# untitled.net
KiCad netlist of a schematic drawn in EAGLE
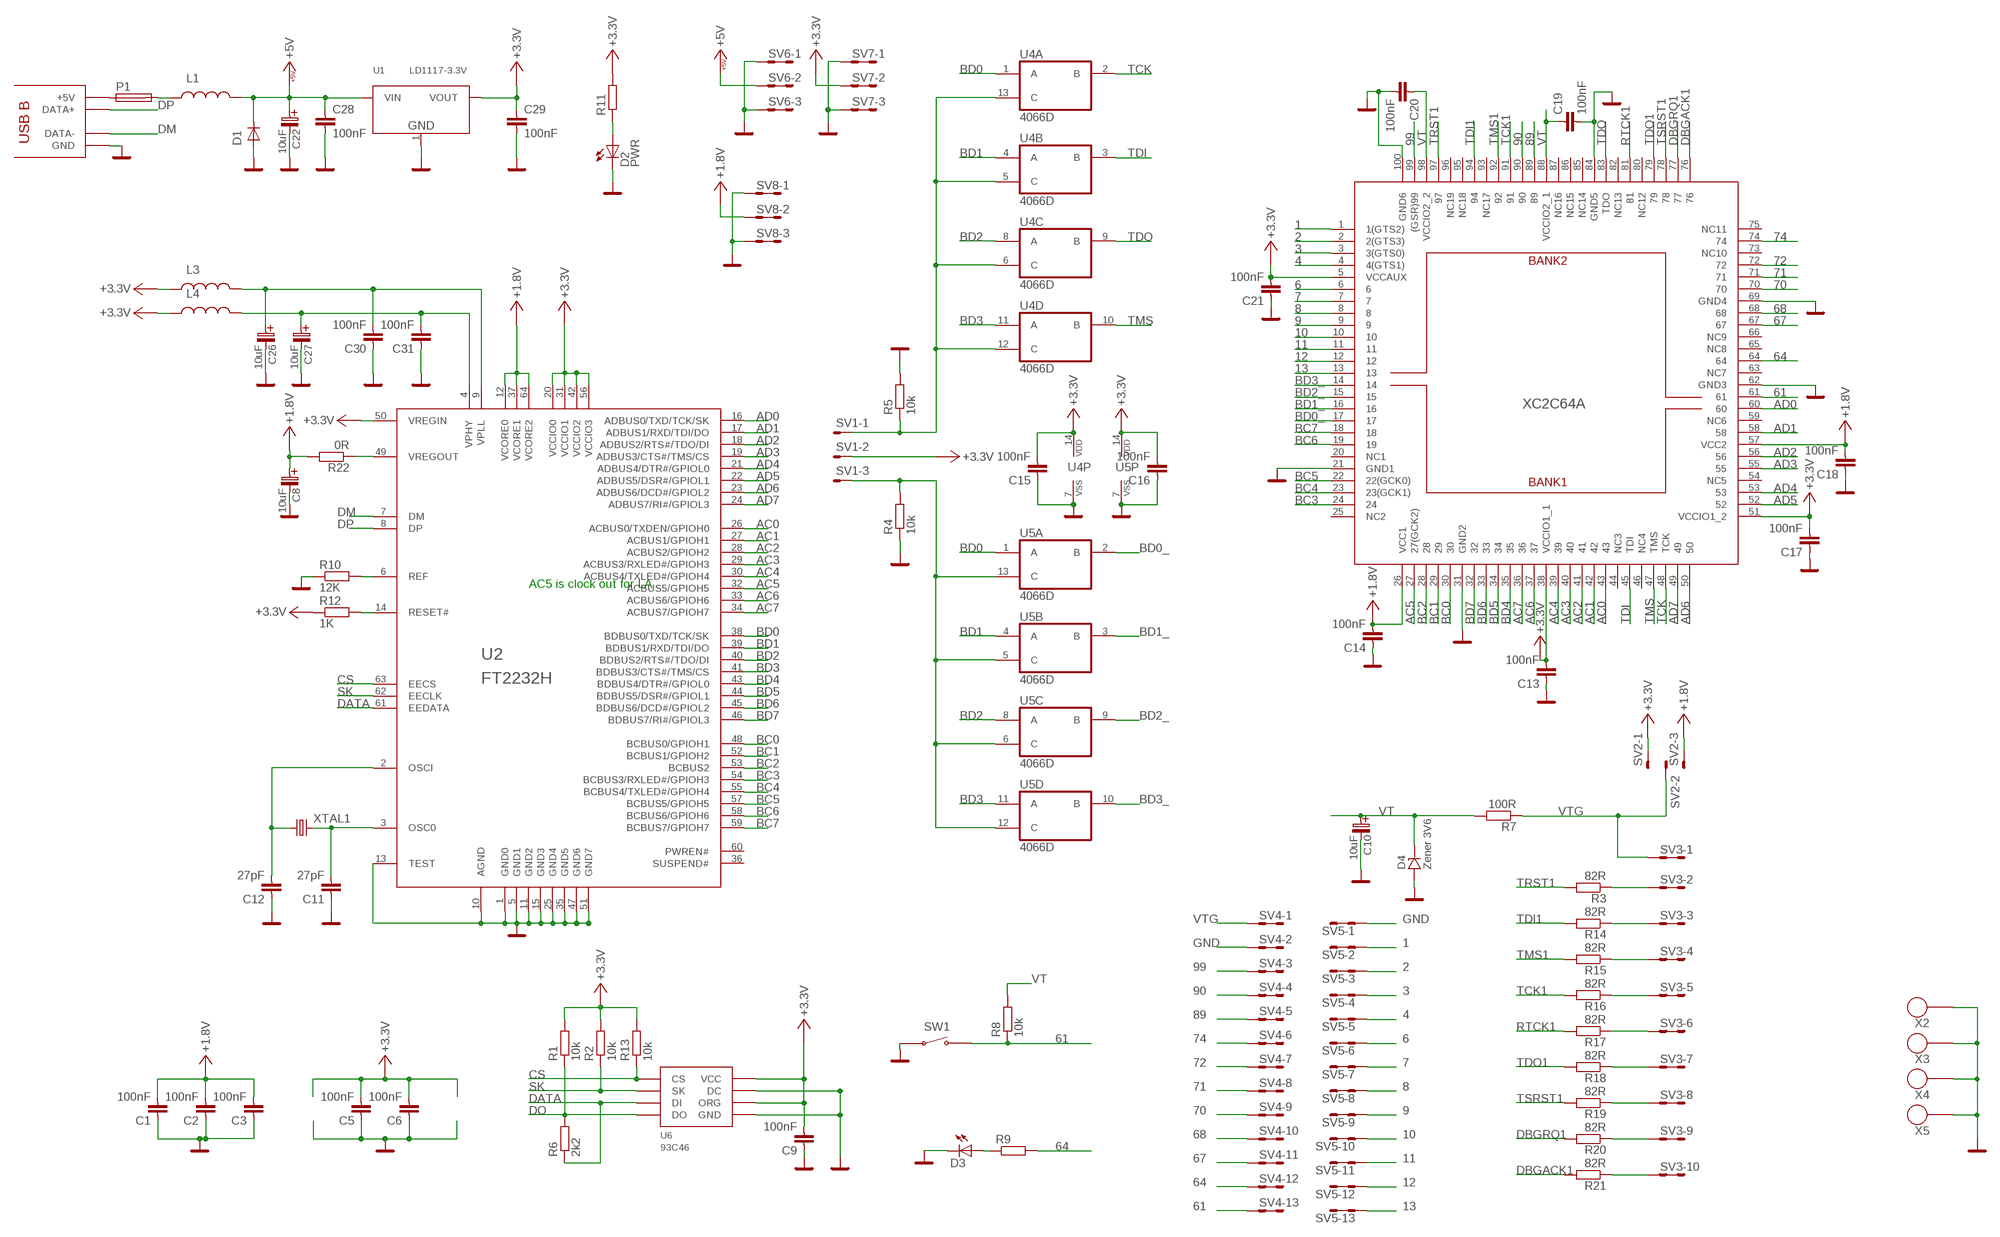
[diagram p0: schematic, sheet 1]

(export (version "E")
  (design (tool "Eeschema 10.0.6"))
  (components
    (comp (ref "C1")
      (value "100nF")
      (footprint "eagle-import:C0805")
      (libsource (lib "eagle-import") (part "C0805"))
    )
    (comp (ref "C2")
      (value "100nF")
      (footprint "eagle-import:C0805")
      (libsource (lib "eagle-import") (part "C0805"))
    )
    (comp (ref "C3")
      (value "100nF")
      (footprint "eagle-import:C0805")
      (libsource (lib "eagle-import") (part "C0805"))
    )
    (comp (ref "C5")
      (value "100nF")
      (footprint "eagle-import:C0805")
      (libsource (lib "eagle-import") (part "C0805"))
    )
    (comp (ref "C6")
      (value "100nF")
      (footprint "eagle-import:C0805")
      (libsource (lib "eagle-import") (part "C0805"))
    )
    (comp (ref "C8") (value "10uF") (footprint "eagle-import:B") (libsource (lib "eagle-import") (part "B")))
    (comp (ref "C9")
      (value "100nF")
      (footprint "eagle-import:C0805")
      (libsource (lib "eagle-import") (part "C0805"))
    )
    (comp (ref "C10") (value "10uF") (footprint "eagle-import:B") (libsource (lib "eagle-import") (part "B")))
    (comp (ref "C11")
      (value "27pF")
      (footprint "eagle-import:C0805")
      (libsource (lib "eagle-import") (part "C0805"))
    )
    (comp (ref "C12")
      (value "27pF")
      (footprint "eagle-import:C0805")
      (libsource (lib "eagle-import") (part "C0805"))
    )
    (comp (ref "C13")
      (value "100nF")
      (footprint "eagle-import:C0805")
      (libsource (lib "eagle-import") (part "C0805"))
    )
    (comp (ref "C14")
      (value "100nF")
      (footprint "eagle-import:C0805")
      (libsource (lib "eagle-import") (part "C0805"))
    )
    (comp (ref "C15")
      (value "100nF")
      (footprint "eagle-import:C0805")
      (libsource (lib "eagle-import") (part "C0805"))
    )
    (comp (ref "C16")
      (value "100nF")
      (footprint "eagle-import:C0805")
      (libsource (lib "eagle-import") (part "C0805"))
    )
    (comp (ref "C17")
      (value "100nF")
      (footprint "eagle-import:C0805")
      (libsource (lib "eagle-import") (part "C0805"))
    )
    (comp (ref "C18")
      (value "100nF")
      (footprint "eagle-import:C0805")
      (libsource (lib "eagle-import") (part "C0805"))
    )
    (comp (ref "C19")
      (value "100nF")
      (footprint "eagle-import:C0805")
      (libsource (lib "eagle-import") (part "C0805"))
    )
    (comp (ref "C20")
      (value "100nF")
      (footprint "eagle-import:C0805")
      (libsource (lib "eagle-import") (part "C0805"))
    )
    (comp (ref "C21")
      (value "100nF")
      (footprint "eagle-import:C0805")
      (libsource (lib "eagle-import") (part "C0805"))
    )
    (comp (ref "C22") (value "10uF") (footprint "eagle-import:B") (libsource (lib "eagle-import") (part "B")))
    (comp (ref "C26") (value "10uF") (footprint "eagle-import:B") (libsource (lib "eagle-import") (part "B")))
    (comp (ref "C27") (value "10uF") (footprint "eagle-import:B") (libsource (lib "eagle-import") (part "B")))
    (comp (ref "C28")
      (value "100nF")
      (footprint "eagle-import:C0805")
      (libsource (lib "eagle-import") (part "C0805"))
    )
    (comp (ref "C29")
      (value "100nF")
      (footprint "eagle-import:C0805")
      (libsource (lib "eagle-import") (part "C0805"))
    )
    (comp (ref "C30")
      (value "100nF")
      (footprint "eagle-import:C0805")
      (libsource (lib "eagle-import") (part "C0805"))
    )
    (comp (ref "C31")
      (value "100nF")
      (footprint "eagle-import:C0805")
      (libsource (lib "eagle-import") (part "C0805"))
    )
    (comp (ref "D1")
      (value "D-OB.SMA")
      (footprint "eagle-import:SMA")
      (libsource (lib "eagle-import") (part "D-OB.SMA"))
    )
    (comp (ref "D2")
      (value "PWR")
      (footprint "eagle-import:1206")
      (libsource (lib "eagle-import") (part "LED1206"))
    )
    (comp (ref "D3")
      (value "LED1206")
      (footprint "eagle-import:1206")
      (libsource (lib "eagle-import") (part "LED1206"))
    )
    (comp (ref "D4")
      (value "Zener 3V6")
      (footprint "eagle-import:MINIMELF")
      (libsource (lib "eagle-import") (part "D-ZENEROVA"))
    )
    (comp (ref "L1")
      (value "L0805")
      (footprint "eagle-import:L0805")
      (libsource (lib "eagle-import") (part "L0805"))
    )
    (comp (ref "L3")
      (value "L1210")
      (footprint "eagle-import:1210")
      (libsource (lib "eagle-import") (part "L1210"))
    )
    (comp (ref "L4")
      (value "L1210")
      (footprint "eagle-import:1210")
      (libsource (lib "eagle-import") (part "L1210"))
    )
    (comp (ref "P1")
      (value "POJISTKA_1812")
      (footprint "eagle-import:1812")
      (libsource (lib "eagle-import") (part "POJISTKA_1812"))
    )
    (comp (ref "R1")
      (value "10k")
      (footprint "eagle-import:0805")
      (libsource (lib "eagle-import") (part "R0805"))
    )
    (comp (ref "R2")
      (value "10k")
      (footprint "eagle-import:0805")
      (libsource (lib "eagle-import") (part "R0805"))
    )
    (comp (ref "R3")
      (value "82R")
      (footprint "eagle-import:0805")
      (libsource (lib "eagle-import") (part "R0805"))
    )
    (comp (ref "R4")
      (value "10k")
      (footprint "eagle-import:0805")
      (libsource (lib "eagle-import") (part "R0805"))
    )
    (comp (ref "R5")
      (value "10k")
      (footprint "eagle-import:0805")
      (libsource (lib "eagle-import") (part "R0805"))
    )
    (comp (ref "R6")
      (value "2k2")
      (footprint "eagle-import:0805")
      (libsource (lib "eagle-import") (part "R0805"))
    )
    (comp (ref "R7")
      (value "100R")
      (footprint "eagle-import:0805")
      (libsource (lib "eagle-import") (part "R0805"))
    )
    (comp (ref "R8")
      (value "10k")
      (footprint "eagle-import:0805")
      (libsource (lib "eagle-import") (part "R0805"))
    )
    (comp (ref "R9")
      (value "R0805")
      (footprint "eagle-import:0805")
      (libsource (lib "eagle-import") (part "R0805"))
    )
    (comp (ref "R10")
      (value "12K")
      (footprint "eagle-import:0805")
      (libsource (lib "eagle-import") (part "R0805"))
    )
    (comp (ref "R11")
      (value "R0805")
      (footprint "eagle-import:0805")
      (libsource (lib "eagle-import") (part "R0805"))
    )
    (comp (ref "R12")
      (value "1K")
      (footprint "eagle-import:0805")
      (libsource (lib "eagle-import") (part "R0805"))
    )
    (comp (ref "R13")
      (value "10k")
      (footprint "eagle-import:0805")
      (libsource (lib "eagle-import") (part "R0805"))
    )
    (comp (ref "R14")
      (value "82R")
      (footprint "eagle-import:0805")
      (libsource (lib "eagle-import") (part "R0805"))
    )
    (comp (ref "R15")
      (value "82R")
      (footprint "eagle-import:0805")
      (libsource (lib "eagle-import") (part "R0805"))
    )
    (comp (ref "R16")
      (value "82R")
      (footprint "eagle-import:0805")
      (libsource (lib "eagle-import") (part "R0805"))
    )
    (comp (ref "R17")
      (value "82R")
      (footprint "eagle-import:0805")
      (libsource (lib "eagle-import") (part "R0805"))
    )
    (comp (ref "R18")
      (value "82R")
      (footprint "eagle-import:0805")
      (libsource (lib "eagle-import") (part "R0805"))
    )
    (comp (ref "R19")
      (value "82R")
      (footprint "eagle-import:0805")
      (libsource (lib "eagle-import") (part "R0805"))
    )
    (comp (ref "R20")
      (value "82R")
      (footprint "eagle-import:0805")
      (libsource (lib "eagle-import") (part "R0805"))
    )
    (comp (ref "R21")
      (value "82R")
      (footprint "eagle-import:0805")
      (libsource (lib "eagle-import") (part "R0805"))
    )
    (comp (ref "R22")
      (value "0R")
      (footprint "eagle-import:0805")
      (libsource (lib "eagle-import") (part "R0805"))
    )
    (comp (ref "SV1")
      (value "MA03-1")
      (footprint "eagle-import:MA03-1")
      (libsource (lib "eagle-import") (part "MA03-1"))
    )
    (comp (ref "SV2")
      (value "MA03-1")
      (footprint "eagle-import:MA03-1")
      (libsource (lib "eagle-import") (part "MA03-1"))
    )
    (comp (ref "SV3")
      (value "MA10-2")
      (footprint "eagle-import:MA10-2")
      (libsource (lib "eagle-import") (part "MA10-2"))
    )
    (comp (ref "SV4")
      (value "MA13-2")
      (footprint "eagle-import:MA13-2")
      (libsource (lib "eagle-import") (part "MA13-2"))
    )
    (comp (ref "SV5")
      (value "MA13-2")
      (footprint "eagle-import:MA13-2")
      (libsource (lib "eagle-import") (part "MA13-2"))
    )
    (comp (ref "SV6")
      (value "MA03-2")
      (footprint "eagle-import:MA03-2")
      (libsource (lib "eagle-import") (part "MA03-2"))
    )
    (comp (ref "SV7")
      (value "MA03-2")
      (footprint "eagle-import:MA03-2")
      (libsource (lib "eagle-import") (part "MA03-2"))
    )
    (comp (ref "SV8")
      (value "MA03-2")
      (footprint "eagle-import:MA03-2")
      (libsource (lib "eagle-import") (part "MA03-2"))
    )
    (comp (ref "SW1")
      (value "TACT-64K")
      (footprint "eagle-import:TACT-64K")
      (libsource (lib "eagle-import") (part "TACT-64K"))
    )
    (comp (ref "U1")
      (value "LD1117-3.3V")
      (footprint "eagle-import:SOT223")
      (libsource (lib "eagle-import") (part "LD1117-3.3SOT223"))
    )
    (comp (ref "U2")
      (value "FT2232H")
      (footprint "eagle-import:LQFP64")
      (libsource (lib "eagle-import") (part "FT2232H"))
    )
    (comp (ref "U3")
      (value "XC2C64A")
      (footprint "eagle-import:VQ100")
      (libsource (lib "eagle-import") (part "XC2C64A"))
    )
    (comp (ref "U4")
      (value "4066D")
      (footprint "eagle-import:SO14")
      (libsource (lib "eagle-import") (part "4066D"))
    )
    (comp (ref "U5")
      (value "4066D")
      (footprint "eagle-import:SO14")
      (libsource (lib "eagle-import") (part "4066D"))
    )
    (comp (ref "U6")
      (value "93C46")
      (footprint "eagle-import:SOIC8")
      (libsource (lib "eagle-import") (part "93C46"))
    )
    (comp (ref "X1")
      (value "USB_B")
      (footprint "eagle-import:USB_B")
      (libsource (lib "eagle-import") (part "USB_B"))
    )
    (comp (ref "X2")
      (value "SROUB3M")
      (footprint "eagle-import:SROUB3M")
      (libsource (lib "eagle-import") (part "SROUB3M"))
    )
    (comp (ref "X3")
      (value "SROUB3M")
      (footprint "eagle-import:SROUB3M")
      (libsource (lib "eagle-import") (part "SROUB3M"))
    )
    (comp (ref "X4")
      (value "SROUB3M")
      (footprint "eagle-import:SROUB3M")
      (libsource (lib "eagle-import") (part "SROUB3M"))
    )
    (comp (ref "X5")
      (value "SROUB3M")
      (footprint "eagle-import:SROUB3M")
      (libsource (lib "eagle-import") (part "SROUB3M"))
    )
    (comp (ref "XTAL1")
      (value "KRYSLAL_S49")
      (footprint "eagle-import:S49")
      (libsource (lib "eagle-import") (part "KRYSLAL_S49"))
    )
  )
  (nets
    (net (code "1") (name "+1.8V") (class "Default")
      (node (ref "C1") (pin "2") (pinfunction "2_2") (pintype "passive"))
      (node (ref "C14") (pin "2") (pinfunction "2_2") (pintype "passive"))
      (node (ref "C18") (pin "2") (pinfunction "2_2") (pintype "passive"))
      (node (ref "C2") (pin "2") (pinfunction "2_2") (pintype "passive"))
      (node (ref "C3") (pin "2") (pinfunction "2_2") (pintype "passive"))
      (node (ref "C8") (pin "+") (pinfunction "C_EL+_+") (pintype "passive"))
      (node (ref "R22") (pin "2") (pinfunction "2_2") (pintype "passive"))
      (node (ref "SV2") (pin "3") (pinfunction "P$1_3") (pintype "passive"))
      (node (ref "SV8") (pin "3") (pinfunction "K_3") (pintype "passive"))
      (node (ref "SV8") (pin "4") (pinfunction "K_4") (pintype "passive"))
      (node (ref "U2") (pin "12") (pinfunction "VCORE0_12") (pintype "bidirectional"))
      (node (ref "U2") (pin "37") (pinfunction "VCORE1_37") (pintype "bidirectional"))
      (node (ref "U2") (pin "64") (pinfunction "VCORE2_64") (pintype "bidirectional"))
      (node (ref "U3") (pin "26") (pinfunction "VCC1_26") (pintype "bidirectional"))
      (node (ref "U3") (pin "57") (pinfunction "VCC2_57") (pintype "bidirectional"))
    )
    (net (code "2") (name "+3.3V") (class "Default")
      (node (ref "C13") (pin "2") (pinfunction "2_2") (pintype "passive"))
      (node (ref "C15") (pin "2") (pinfunction "2_2") (pintype "passive"))
      (node (ref "C16") (pin "2") (pinfunction "2_2") (pintype "passive"))
      (node (ref "C17") (pin "2") (pinfunction "2_2") (pintype "passive"))
      (node (ref "C21") (pin "2") (pinfunction "2_2") (pintype "passive"))
      (node (ref "C29") (pin "1") (pinfunction "1_1") (pintype "passive"))
      (node (ref "C5") (pin "2") (pinfunction "2_2") (pintype "passive"))
      (node (ref "C6") (pin "2") (pinfunction "2_2") (pintype "passive"))
      (node (ref "C9") (pin "2") (pinfunction "2_2") (pintype "passive"))
      (node (ref "L3") (pin "P$1") (pinfunction "1_P$1") (pintype "passive"))
      (node (ref "L4") (pin "P$1") (pinfunction "1_P$1") (pintype "passive"))
      (node (ref "R1") (pin "2") (pinfunction "2_2") (pintype "passive"))
      (node (ref "R11") (pin "2") (pinfunction "2_2") (pintype "passive"))
      (node (ref "R12") (pin "1") (pinfunction "1_1") (pintype "passive"))
      (node (ref "R13") (pin "2") (pinfunction "2_2") (pintype "passive"))
      (node (ref "R2") (pin "2") (pinfunction "2_2") (pintype "passive"))
      (node (ref "SV1") (pin "2") (pinfunction "P$1_2") (pintype "passive"))
      (node (ref "SV2") (pin "1") (pinfunction "P$1_1") (pintype "passive"))
      (node (ref "SV7") (pin "3") (pinfunction "K_3") (pintype "passive"))
      (node (ref "SV7") (pin "4") (pinfunction "K_4") (pintype "passive"))
      (node (ref "U1") (pin "2") (pinfunction "VOUT_2") (pintype "bidirectional"))
      (node (ref "U2") (pin "20") (pinfunction "VCCIO0_20") (pintype "bidirectional"))
      (node (ref "U2") (pin "31") (pinfunction "VCCIO1_31") (pintype "bidirectional"))
      (node (ref "U2") (pin "42") (pinfunction "VCCIO2_42") (pintype "bidirectional"))
      (node (ref "U2") (pin "50") (pinfunction "VREGIN_50") (pintype "bidirectional"))
      (node (ref "U2") (pin "56") (pinfunction "VCCIO3_56") (pintype "bidirectional"))
      (node (ref "U3") (pin "38") (pinfunction "VCCIO1_1_38") (pintype "bidirectional"))
      (node (ref "U3") (pin "5") (pinfunction "VCCAUX_5") (pintype "bidirectional"))
      (node (ref "U3") (pin "51") (pinfunction "VCCIO1_2_51") (pintype "bidirectional"))
      (node (ref "U4") (pin "14") (pinfunction "VDD_14") (pintype "power_in"))
      (node (ref "U5") (pin "14") (pinfunction "VDD_14") (pintype "power_in"))
      (node (ref "U6") (pin "6") (pinfunction "ORG_6") (pintype "bidirectional"))
      (node (ref "U6") (pin "8") (pinfunction "VCC_8") (pintype "bidirectional"))
    )
    (net (code "3") (name "+5V") (class "Default")
      (node (ref "C22") (pin "+") (pinfunction "C_EL+_+") (pintype "passive"))
      (node (ref "C28") (pin "1") (pinfunction "1_1") (pintype "passive"))
      (node (ref "D1") (pin "K") (pinfunction "C_K") (pintype "passive"))
      (node (ref "L1") (pin "2") (pinfunction "2_2") (pintype "passive"))
      (node (ref "SV6") (pin "3") (pinfunction "K_3") (pintype "passive"))
      (node (ref "SV6") (pin "4") (pinfunction "K_4") (pintype "passive"))
      (node (ref "U1") (pin "3") (pinfunction "VIN_3") (pintype "bidirectional"))
    )
    (net (code "4") (name "/1") (class "Default")
      (node (ref "SV5") (pin "3") (pinfunction "K_3") (pintype "passive"))
      (node (ref "SV5") (pin "4") (pinfunction "K_4") (pintype "passive"))
      (node (ref "U3") (pin "1") (pinfunction "1(GTS2)_1") (pintype "bidirectional"))
    )
    (net (code "5") (name "/2") (class "Default")
      (node (ref "SV5") (pin "5") (pinfunction "K_5") (pintype "passive"))
      (node (ref "SV5") (pin "6") (pinfunction "K_6") (pintype "passive"))
      (node (ref "U3") (pin "2") (pinfunction "2(GTS3)_2") (pintype "bidirectional"))
    )
    (net (code "6") (name "/3") (class "Default")
      (node (ref "SV5") (pin "7") (pinfunction "K_7") (pintype "passive"))
      (node (ref "SV5") (pin "8") (pinfunction "K_8") (pintype "passive"))
      (node (ref "U3") (pin "3") (pinfunction "3(GTS0)_3") (pintype "bidirectional"))
    )
    (net (code "7") (name "/4") (class "Default")
      (node (ref "SV5") (pin "10") (pinfunction "K_10") (pintype "passive"))
      (node (ref "SV5") (pin "9") (pinfunction "K_9") (pintype "passive"))
      (node (ref "U3") (pin "4") (pinfunction "4(GTS1)_4") (pintype "bidirectional"))
    )
    (net (code "8") (name "/6") (class "Default")
      (node (ref "SV5") (pin "11") (pinfunction "K_11") (pintype "passive"))
      (node (ref "SV5") (pin "12") (pinfunction "K_12") (pintype "passive"))
      (node (ref "U3") (pin "6") (pinfunction "6_6") (pintype "bidirectional"))
    )
    (net (code "9") (name "/7") (class "Default")
      (node (ref "SV5") (pin "13") (pinfunction "K_13") (pintype "passive"))
      (node (ref "SV5") (pin "14") (pinfunction "K_14") (pintype "passive"))
      (node (ref "U3") (pin "7") (pinfunction "7_7") (pintype "bidirectional"))
    )
    (net (code "10") (name "/8") (class "Default")
      (node (ref "SV5") (pin "15") (pinfunction "K_15") (pintype "passive"))
      (node (ref "SV5") (pin "16") (pinfunction "K_16") (pintype "passive"))
      (node (ref "U3") (pin "8") (pinfunction "8_8") (pintype "bidirectional"))
    )
    (net (code "11") (name "/9") (class "Default")
      (node (ref "SV5") (pin "17") (pinfunction "K_17") (pintype "passive"))
      (node (ref "SV5") (pin "18") (pinfunction "K_18") (pintype "passive"))
      (node (ref "U3") (pin "9") (pinfunction "9_9") (pintype "bidirectional"))
    )
    (net (code "12") (name "/10") (class "Default")
      (node (ref "SV5") (pin "19") (pinfunction "K_19") (pintype "passive"))
      (node (ref "SV5") (pin "20") (pinfunction "K_20") (pintype "passive"))
      (node (ref "U3") (pin "10") (pinfunction "10_10") (pintype "bidirectional"))
    )
    (net (code "13") (name "/11") (class "Default")
      (node (ref "SV5") (pin "21") (pinfunction "K_21") (pintype "passive"))
      (node (ref "SV5") (pin "22") (pinfunction "K_22") (pintype "passive"))
      (node (ref "U3") (pin "11") (pinfunction "11_11") (pintype "bidirectional"))
    )
    (net (code "14") (name "/12") (class "Default")
      (node (ref "SV5") (pin "23") (pinfunction "K_23") (pintype "passive"))
      (node (ref "SV5") (pin "24") (pinfunction "K_24") (pintype "passive"))
      (node (ref "U3") (pin "12") (pinfunction "12_12") (pintype "bidirectional"))
    )
    (net (code "15") (name "/13") (class "Default")
      (node (ref "SV5") (pin "25") (pinfunction "K_25") (pintype "passive"))
      (node (ref "SV5") (pin "26") (pinfunction "K_26") (pintype "passive"))
      (node (ref "U3") (pin "13") (pinfunction "13_13") (pintype "bidirectional"))
    )
    (net (code "16") (name "/61") (class "Default")
      (node (ref "R8") (pin "1") (pinfunction "1_1") (pintype "passive"))
      (node (ref "SV4") (pin "25") (pinfunction "K_25") (pintype "passive"))
      (node (ref "SV4") (pin "26") (pinfunction "K_26") (pintype "passive"))
      (node (ref "SW1") (pin "P$3") (pinfunction "P$2_P$3") (pintype "passive"))
      (node (ref "SW1") (pin "P$4") (pinfunction "P$2_P$4") (pintype "passive"))
      (node (ref "U3") (pin "61") (pinfunction "61_61") (pintype "bidirectional"))
    )
    (net (code "17") (name "/64") (class "Default")
      (node (ref "R9") (pin "2") (pinfunction "2_2") (pintype "passive"))
      (node (ref "SV4") (pin "23") (pinfunction "K_23") (pintype "passive"))
      (node (ref "SV4") (pin "24") (pinfunction "K_24") (pintype "passive"))
      (node (ref "U3") (pin "64") (pinfunction "64_64") (pintype "bidirectional"))
    )
    (net (code "18") (name "/67") (class "Default")
      (node (ref "SV4") (pin "21") (pinfunction "K_21") (pintype "passive"))
      (node (ref "SV4") (pin "22") (pinfunction "K_22") (pintype "passive"))
      (node (ref "U3") (pin "67") (pinfunction "67_67") (pintype "bidirectional"))
    )
    (net (code "19") (name "/68") (class "Default")
      (node (ref "SV4") (pin "19") (pinfunction "K_19") (pintype "passive"))
      (node (ref "SV4") (pin "20") (pinfunction "K_20") (pintype "passive"))
      (node (ref "U3") (pin "68") (pinfunction "68_68") (pintype "bidirectional"))
    )
    (net (code "20") (name "/70") (class "Default")
      (node (ref "SV4") (pin "17") (pinfunction "K_17") (pintype "passive"))
      (node (ref "SV4") (pin "18") (pinfunction "K_18") (pintype "passive"))
      (node (ref "U3") (pin "70") (pinfunction "70_70") (pintype "bidirectional"))
    )
    (net (code "21") (name "/71") (class "Default")
      (node (ref "SV4") (pin "15") (pinfunction "K_15") (pintype "passive"))
      (node (ref "SV4") (pin "16") (pinfunction "K_16") (pintype "passive"))
      (node (ref "U3") (pin "71") (pinfunction "71_71") (pintype "bidirectional"))
    )
    (net (code "22") (name "/72") (class "Default")
      (node (ref "SV4") (pin "13") (pinfunction "K_13") (pintype "passive"))
      (node (ref "SV4") (pin "14") (pinfunction "K_14") (pintype "passive"))
      (node (ref "U3") (pin "72") (pinfunction "72_72") (pintype "bidirectional"))
    )
    (net (code "23") (name "/74") (class "Default")
      (node (ref "SV4") (pin "11") (pinfunction "K_11") (pintype "passive"))
      (node (ref "SV4") (pin "12") (pinfunction "K_12") (pintype "passive"))
      (node (ref "U3") (pin "74") (pinfunction "74_74") (pintype "bidirectional"))
    )
    (net (code "24") (name "/89") (class "Default")
      (node (ref "SV4") (pin "10") (pinfunction "K_10") (pintype "passive"))
      (node (ref "SV4") (pin "9") (pinfunction "K_9") (pintype "passive"))
      (node (ref "U3") (pin "89") (pinfunction "89_89") (pintype "bidirectional"))
    )
    (net (code "25") (name "/90") (class "Default")
      (node (ref "SV4") (pin "7") (pinfunction "K_7") (pintype "passive"))
      (node (ref "SV4") (pin "8") (pinfunction "K_8") (pintype "passive"))
      (node (ref "U3") (pin "90") (pinfunction "90_90") (pintype "bidirectional"))
    )
    (net (code "26") (name "/99") (class "Default")
      (node (ref "SV4") (pin "5") (pinfunction "K_5") (pintype "passive"))
      (node (ref "SV4") (pin "6") (pinfunction "K_6") (pintype "passive"))
      (node (ref "U3") (pin "99") (pinfunction "(GSR)99_99") (pintype "bidirectional"))
    )
    (net (code "27") (name "/AC0") (class "Default")
      (node (ref "U2") (pin "26") (pinfunction "ACBUS0/TXDEN/GPIOH0_26") (pintype "bidirectional"))
      (node (ref "U3") (pin "43") (pinfunction "43_43") (pintype "bidirectional"))
    )
    (net (code "28") (name "/AC1") (class "Default")
      (node (ref "U2") (pin "27") (pinfunction "ACBUS1/GPIOH1_27") (pintype "bidirectional"))
      (node (ref "U3") (pin "42") (pinfunction "42_42") (pintype "bidirectional"))
    )
    (net (code "29") (name "/AC2") (class "Default")
      (node (ref "U2") (pin "28") (pinfunction "ACBUS2/GPIOH2_28") (pintype "bidirectional"))
      (node (ref "U3") (pin "41") (pinfunction "41_41") (pintype "bidirectional"))
    )
    (net (code "30") (name "/AC3") (class "Default")
      (node (ref "U2") (pin "29") (pinfunction "ACBUS3/RXLED#/GPIOH3_29") (pintype "bidirectional"))
      (node (ref "U3") (pin "40") (pinfunction "40_40") (pintype "bidirectional"))
    )
    (net (code "31") (name "/AC4") (class "Default")
      (node (ref "U2") (pin "30") (pinfunction "ACBUS4/TXLED#/GPIOH4_30") (pintype "bidirectional"))
      (node (ref "U3") (pin "39") (pinfunction "39_39") (pintype "bidirectional"))
    )
    (net (code "32") (name "/AC5") (class "Default")
      (node (ref "U2") (pin "32") (pinfunction "ACBUS5/GPIOH5_32") (pintype "bidirectional"))
      (node (ref "U3") (pin "27") (pinfunction "27(GCK2)_27") (pintype "bidirectional"))
    )
    (net (code "33") (name "/AC6") (class "Default")
      (node (ref "U2") (pin "33") (pinfunction "ACBUS6/GPIOH6_33") (pintype "bidirectional"))
      (node (ref "U3") (pin "37") (pinfunction "37_37") (pintype "bidirectional"))
    )
    (net (code "34") (name "/AC7") (class "Default")
      (node (ref "U2") (pin "34") (pinfunction "ACBUS7/GPIOH7_34") (pintype "bidirectional"))
      (node (ref "U3") (pin "36") (pinfunction "36_36") (pintype "bidirectional"))
    )
    (net (code "35") (name "/AD0") (class "Default")
      (node (ref "U2") (pin "16") (pinfunction "ADBUS0/TXD/TCK/SK_16") (pintype "bidirectional"))
      (node (ref "U3") (pin "60") (pinfunction "60_60") (pintype "bidirectional"))
    )
    (net (code "36") (name "/AD1") (class "Default")
      (node (ref "U2") (pin "17") (pinfunction "ADBUS1/RXD/TDI/DO_17") (pintype "bidirectional"))
      (node (ref "U3") (pin "58") (pinfunction "58_58") (pintype "bidirectional"))
    )
    (net (code "37") (name "/AD2") (class "Default")
      (node (ref "U2") (pin "18") (pinfunction "ADBUS2/RTS#/TDO/DI_18") (pintype "bidirectional"))
      (node (ref "U3") (pin "56") (pinfunction "56_56") (pintype "bidirectional"))
    )
    (net (code "38") (name "/AD3") (class "Default")
      (node (ref "U2") (pin "19") (pinfunction "ADBUS3/CTS#/TMS/CS_19") (pintype "bidirectional"))
      (node (ref "U3") (pin "55") (pinfunction "55_55") (pintype "bidirectional"))
    )
    (net (code "39") (name "/AD4") (class "Default")
      (node (ref "U2") (pin "21") (pinfunction "ADBUS4/DTR#/GPIOL0_21") (pintype "bidirectional"))
      (node (ref "U3") (pin "53") (pinfunction "53_53") (pintype "bidirectional"))
    )
    (net (code "40") (name "/AD5") (class "Default")
      (node (ref "U2") (pin "22") (pinfunction "ADBUS5/DSR#/GPIOL1_22") (pintype "bidirectional"))
      (node (ref "U3") (pin "52") (pinfunction "52_52") (pintype "bidirectional"))
    )
    (net (code "41") (name "/AD6") (class "Default")
      (node (ref "U2") (pin "23") (pinfunction "ADBUS6/DCD#/GPIOL2_23") (pintype "bidirectional"))
      (node (ref "U3") (pin "50") (pinfunction "50_50") (pintype "bidirectional"))
    )
    (net (code "42") (name "/AD7") (class "Default")
      (node (ref "U2") (pin "24") (pinfunction "ADBUS7/RI#/GPIOL3_24") (pintype "bidirectional"))
      (node (ref "U3") (pin "49") (pinfunction "49_49") (pintype "bidirectional"))
    )
    (net (code "43") (name "/BC0") (class "Default")
      (node (ref "U2") (pin "48") (pinfunction "BCBUS0/GPIOH1_48") (pintype "bidirectional"))
      (node (ref "U3") (pin "30") (pinfunction "30_30") (pintype "bidirectional"))
    )
    (net (code "44") (name "/BC1") (class "Default")
      (node (ref "U2") (pin "52") (pinfunction "BCBUS1/GPIOH2_52") (pintype "bidirectional"))
      (node (ref "U3") (pin "29") (pinfunction "29_29") (pintype "bidirectional"))
    )
    (net (code "45") (name "/BC2") (class "Default")
      (node (ref "U2") (pin "53") (pinfunction "BCBUS2_53") (pintype "bidirectional"))
      (node (ref "U3") (pin "28") (pinfunction "28_28") (pintype "bidirectional"))
    )
    (net (code "46") (name "/BC3") (class "Default")
      (node (ref "U2") (pin "54") (pinfunction "BCBUS3/RXLED#/GPIOH3_54") (pintype "bidirectional"))
      (node (ref "U3") (pin "24") (pinfunction "24_24") (pintype "bidirectional"))
    )
    (net (code "47") (name "/BC4") (class "Default")
      (node (ref "U2") (pin "55") (pinfunction "BCBUS4/TXLED#/GPIOH4_55") (pintype "bidirectional"))
      (node (ref "U3") (pin "23") (pinfunction "23(GCK1)_23") (pintype "bidirectional"))
    )
    (net (code "48") (name "/BC5") (class "Default")
      (node (ref "U2") (pin "57") (pinfunction "BCBUS5/GPIOH5_57") (pintype "bidirectional"))
      (node (ref "U3") (pin "22") (pinfunction "22(GCK0)_22") (pintype "bidirectional"))
    )
    (net (code "49") (name "/BC6") (class "Default")
      (node (ref "U2") (pin "58") (pinfunction "BCBUS6/GPIOH6_58") (pintype "bidirectional"))
      (node (ref "U3") (pin "19") (pinfunction "19_19") (pintype "bidirectional"))
    )
    (net (code "50") (name "/BC7") (class "Default")
      (node (ref "U2") (pin "59") (pinfunction "BCBUS7/GPIOH7_59") (pintype "bidirectional"))
      (node (ref "U3") (pin "18") (pinfunction "18_18") (pintype "bidirectional"))
    )
    (net (code "51") (name "/BD0") (class "Default")
      (node (ref "U2") (pin "38") (pinfunction "BDBUS0/TXD/TCK/SK_38") (pintype "bidirectional"))
      (node (ref "U4") (pin "1") (pinfunction "A_1") (pintype "tri_state"))
      (node (ref "U5") (pin "1") (pinfunction "A_1") (pintype "tri_state"))
    )
    (net (code "52") (name "/BD0_") (class "Default")
      (node (ref "U3") (pin "17") (pinfunction "17_17") (pintype "bidirectional"))
      (node (ref "U5") (pin "2") (pinfunction "B_2") (pintype "tri_state"))
    )
    (net (code "53") (name "/BD1") (class "Default")
      (node (ref "U2") (pin "39") (pinfunction "BDBUS1/RXD/TDI/DO_39") (pintype "bidirectional"))
      (node (ref "U4") (pin "4") (pinfunction "A_4") (pintype "tri_state"))
      (node (ref "U5") (pin "4") (pinfunction "A_4") (pintype "tri_state"))
    )
    (net (code "54") (name "/BD1_") (class "Default")
      (node (ref "U3") (pin "16") (pinfunction "16_16") (pintype "bidirectional"))
      (node (ref "U5") (pin "3") (pinfunction "B_3") (pintype "tri_state"))
    )
    (net (code "55") (name "/BD2") (class "Default")
      (node (ref "U2") (pin "40") (pinfunction "BDBUS2/RTS#/TDO/DI_40") (pintype "bidirectional"))
      (node (ref "U4") (pin "8") (pinfunction "A_8") (pintype "tri_state"))
      (node (ref "U5") (pin "8") (pinfunction "A_8") (pintype "tri_state"))
    )
    (net (code "56") (name "/BD2_") (class "Default")
      (node (ref "U3") (pin "15") (pinfunction "15_15") (pintype "bidirectional"))
      (node (ref "U5") (pin "9") (pinfunction "B_9") (pintype "tri_state"))
    )
    (net (code "57") (name "/BD3") (class "Default")
      (node (ref "U2") (pin "41") (pinfunction "BDBUS3/CTS#/TMS/CS_41") (pintype "bidirectional"))
      (node (ref "U4") (pin "11") (pinfunction "A_11") (pintype "tri_state"))
      (node (ref "U5") (pin "11") (pinfunction "A_11") (pintype "tri_state"))
    )
    (net (code "58") (name "/BD3_") (class "Default")
      (node (ref "U3") (pin "14") (pinfunction "14_14") (pintype "bidirectional"))
      (node (ref "U5") (pin "10") (pinfunction "B_10") (pintype "tri_state"))
    )
    (net (code "59") (name "/BD4") (class "Default")
      (node (ref "U2") (pin "43") (pinfunction "BDBUS4/DTR#/GPIOL0_43") (pintype "bidirectional"))
      (node (ref "U3") (pin "35") (pinfunction "35_35") (pintype "bidirectional"))
    )
    (net (code "60") (name "/BD5") (class "Default")
      (node (ref "U2") (pin "44") (pinfunction "BDBUS5/DSR#/GPIOL1_44") (pintype "bidirectional"))
      (node (ref "U3") (pin "34") (pinfunction "34_34") (pintype "bidirectional"))
    )
    (net (code "61") (name "/BD6") (class "Default")
      (node (ref "U2") (pin "45") (pinfunction "BDBUS6/DCD#/GPIOL2_45") (pintype "bidirectional"))
      (node (ref "U3") (pin "33") (pinfunction "33_33") (pintype "bidirectional"))
    )
    (net (code "62") (name "/BD7") (class "Default")
      (node (ref "U2") (pin "46") (pinfunction "BDBUS7/RI#/GPIOL3_46") (pintype "bidirectional"))
      (node (ref "U3") (pin "32") (pinfunction "32_32") (pintype "bidirectional"))
    )
    (net (code "63") (name "/CS") (class "Default")
      (node (ref "R13") (pin "1") (pinfunction "1_1") (pintype "passive"))
      (node (ref "U2") (pin "63") (pinfunction "EECS_63") (pintype "bidirectional"))
      (node (ref "U6") (pin "1") (pinfunction "CS_1") (pintype "bidirectional"))
    )
    (net (code "64") (name "/DATA") (class "Default")
      (node (ref "R6") (pin "1") (pinfunction "1_1") (pintype "passive"))
      (node (ref "U2") (pin "61") (pinfunction "EEDATA_61") (pintype "bidirectional"))
      (node (ref "U6") (pin "3") (pinfunction "DI_3") (pintype "bidirectional"))
    )
    (net (code "65") (name "/DBGACK1") (class "Default")
      (node (ref "R21") (pin "2") (pinfunction "2_2") (pintype "passive"))
      (node (ref "U3") (pin "76") (pinfunction "76_76") (pintype "bidirectional"))
    )
    (net (code "66") (name "/DBGRQ1") (class "Default")
      (node (ref "R20") (pin "2") (pinfunction "2_2") (pintype "passive"))
      (node (ref "U3") (pin "77") (pinfunction "77_77") (pintype "bidirectional"))
    )
    (net (code "67") (name "/DM") (class "Default")
      (node (ref "U2") (pin "7") (pinfunction "DM_7") (pintype "bidirectional"))
      (node (ref "X1") (pin "2") (pinfunction "DATA-_2") (pintype "bidirectional"))
    )
    (net (code "68") (name "/DO") (class "Default")
      (node (ref "R1") (pin "1") (pinfunction "1_1") (pintype "passive"))
      (node (ref "R6") (pin "2") (pinfunction "2_2") (pintype "passive"))
      (node (ref "U6") (pin "4") (pinfunction "DO_4") (pintype "bidirectional"))
    )
    (net (code "69") (name "/DP") (class "Default")
      (node (ref "U2") (pin "8") (pinfunction "DP_8") (pintype "bidirectional"))
      (node (ref "X1") (pin "3") (pinfunction "DATA+_3") (pintype "bidirectional"))
    )
    (net (code "70") (name "/RTCK1") (class "Default")
      (node (ref "R17") (pin "2") (pinfunction "2_2") (pintype "passive"))
      (node (ref "U3") (pin "81") (pinfunction "81_81") (pintype "bidirectional"))
    )
    (net (code "71") (name "/SK") (class "Default")
      (node (ref "R2") (pin "1") (pinfunction "1_1") (pintype "passive"))
      (node (ref "U2") (pin "62") (pinfunction "EECLK_62") (pintype "bidirectional"))
      (node (ref "U6") (pin "2") (pinfunction "SK_2") (pintype "bidirectional"))
    )
    (net (code "72") (name "/TCK") (class "Default")
      (node (ref "U3") (pin "48") (pinfunction "TCK_48") (pintype "bidirectional"))
      (node (ref "U4") (pin "2") (pinfunction "B_2") (pintype "tri_state"))
    )
    (net (code "73") (name "/TCK1") (class "Default")
      (node (ref "R16") (pin "2") (pinfunction "2_2") (pintype "passive"))
      (node (ref "U3") (pin "91") (pinfunction "91_91") (pintype "bidirectional"))
    )
    (net (code "74") (name "/TDI") (class "Default")
      (node (ref "U3") (pin "45") (pinfunction "TDI_45") (pintype "bidirectional"))
      (node (ref "U4") (pin "3") (pinfunction "B_3") (pintype "tri_state"))
    )
    (net (code "75") (name "/TDI1") (class "Default")
      (node (ref "R14") (pin "2") (pinfunction "2_2") (pintype "passive"))
      (node (ref "U3") (pin "94") (pinfunction "94_94") (pintype "bidirectional"))
    )
    (net (code "76") (name "/TDO") (class "Default")
      (node (ref "U3") (pin "83") (pinfunction "TDO_83") (pintype "bidirectional"))
      (node (ref "U4") (pin "9") (pinfunction "B_9") (pintype "tri_state"))
    )
    (net (code "77") (name "/TDO1") (class "Default")
      (node (ref "R18") (pin "2") (pinfunction "2_2") (pintype "passive"))
      (node (ref "U3") (pin "79") (pinfunction "79_79") (pintype "bidirectional"))
    )
    (net (code "78") (name "/TMS") (class "Default")
      (node (ref "U3") (pin "47") (pinfunction "TMS_47") (pintype "bidirectional"))
      (node (ref "U4") (pin "10") (pinfunction "B_10") (pintype "tri_state"))
    )
    (net (code "79") (name "/TMS1") (class "Default")
      (node (ref "R15") (pin "2") (pinfunction "2_2") (pintype "passive"))
      (node (ref "U3") (pin "92") (pinfunction "92_92") (pintype "bidirectional"))
    )
    (net (code "80") (name "/TRST1") (class "Default")
      (node (ref "R3") (pin "2") (pinfunction "2_2") (pintype "passive"))
      (node (ref "U3") (pin "97") (pinfunction "97_97") (pintype "bidirectional"))
    )
    (net (code "81") (name "/TSRST1") (class "Default")
      (node (ref "R19") (pin "2") (pinfunction "2_2") (pintype "passive"))
      (node (ref "U3") (pin "78") (pinfunction "78_78") (pintype "bidirectional"))
    )
    (net (code "82") (name "/VT") (class "Default")
      (node (ref "C10") (pin "+") (pinfunction "C_EL+_+") (pintype "passive"))
      (node (ref "C19") (pin "1") (pinfunction "1_1") (pintype "passive"))
      (node (ref "C20") (pin "1") (pinfunction "1_1") (pintype "passive"))
      (node (ref "D4") (pin "C") (pinfunction "K_C") (pintype "passive"))
      (node (ref "R7") (pin "2") (pinfunction "2_2") (pintype "passive"))
      (node (ref "R8") (pin "2") (pinfunction "2_2") (pintype "passive"))
      (node (ref "U3") (pin "88") (pinfunction "VCCIO2_1_88") (pintype "bidirectional"))
      (node (ref "U3") (pin "98") (pinfunction "VCCIO2_2_98") (pintype "bidirectional"))
    )
    (net (code "83") (name "/VTG") (class "Default")
      (node (ref "R7") (pin "1") (pinfunction "1_1") (pintype "passive"))
      (node (ref "SV2") (pin "2") (pinfunction "P$1_2") (pintype "passive"))
      (node (ref "SV3") (pin "1") (pinfunction "K_1") (pintype "passive"))
      (node (ref "SV3") (pin "2") (pinfunction "K_2") (pintype "passive"))
      (node (ref "SV4") (pin "1") (pinfunction "K_1") (pintype "passive"))
      (node (ref "SV4") (pin "2") (pinfunction "K_2") (pintype "passive"))
    )
    (net (code "84") (name "GND") (class "Default")
      (node (ref "C1") (pin "1") (pinfunction "1_1") (pintype "passive"))
      (node (ref "C10") (pin "-") (pinfunction "C_EL-_-") (pintype "passive"))
      (node (ref "C11") (pin "1") (pinfunction "1_1") (pintype "passive"))
      (node (ref "C12") (pin "1") (pinfunction "1_1") (pintype "passive"))
      (node (ref "C13") (pin "1") (pinfunction "1_1") (pintype "passive"))
      (node (ref "C14") (pin "1") (pinfunction "1_1") (pintype "passive"))
      (node (ref "C15") (pin "1") (pinfunction "1_1") (pintype "passive"))
      (node (ref "C16") (pin "1") (pinfunction "1_1") (pintype "passive"))
      (node (ref "C17") (pin "1") (pinfunction "1_1") (pintype "passive"))
      (node (ref "C18") (pin "1") (pinfunction "1_1") (pintype "passive"))
      (node (ref "C19") (pin "2") (pinfunction "2_2") (pintype "passive"))
      (node (ref "C2") (pin "1") (pinfunction "1_1") (pintype "passive"))
      (node (ref "C20") (pin "2") (pinfunction "2_2") (pintype "passive"))
      (node (ref "C21") (pin "1") (pinfunction "1_1") (pintype "passive"))
      (node (ref "C22") (pin "-") (pinfunction "C_EL-_-") (pintype "passive"))
      (node (ref "C26") (pin "-") (pinfunction "C_EL-_-") (pintype "passive"))
      (node (ref "C27") (pin "-") (pinfunction "C_EL-_-") (pintype "passive"))
      (node (ref "C28") (pin "2") (pinfunction "2_2") (pintype "passive"))
      (node (ref "C29") (pin "2") (pinfunction "2_2") (pintype "passive"))
      (node (ref "C3") (pin "1") (pinfunction "1_1") (pintype "passive"))
      (node (ref "C30") (pin "1") (pinfunction "1_1") (pintype "passive"))
      (node (ref "C31") (pin "1") (pinfunction "1_1") (pintype "passive"))
      (node (ref "C5") (pin "1") (pinfunction "1_1") (pintype "passive"))
      (node (ref "C6") (pin "1") (pinfunction "1_1") (pintype "passive"))
      (node (ref "C8") (pin "-") (pinfunction "C_EL-_-") (pintype "passive"))
      (node (ref "C9") (pin "1") (pinfunction "1_1") (pintype "passive"))
      (node (ref "D1") (pin "A") (pinfunction "A_A") (pintype "passive"))
      (node (ref "D2") (pin "K") (pinfunction "C_K") (pintype "passive"))
      (node (ref "D3") (pin "K") (pinfunction "C_K") (pintype "passive"))
      (node (ref "D4") (pin "A") (pinfunction "A_A") (pintype "passive"))
      (node (ref "R10") (pin "1") (pinfunction "1_1") (pintype "passive"))
      (node (ref "R4") (pin "1") (pinfunction "1_1") (pintype "passive"))
      (node (ref "R5") (pin "2") (pinfunction "2_2") (pintype "passive"))
      (node (ref "SV4") (pin "3") (pinfunction "K_3") (pintype "passive"))
      (node (ref "SV4") (pin "4") (pinfunction "K_4") (pintype "passive"))
      (node (ref "SV5") (pin "1") (pinfunction "K_1") (pintype "passive"))
      (node (ref "SV5") (pin "2") (pinfunction "K_2") (pintype "passive"))
      (node (ref "SV6") (pin "1") (pinfunction "K_1") (pintype "passive"))
      (node (ref "SV6") (pin "2") (pinfunction "K_2") (pintype "passive"))
      (node (ref "SV6") (pin "5") (pinfunction "K_5") (pintype "passive"))
      (node (ref "SV6") (pin "6") (pinfunction "K_6") (pintype "passive"))
      (node (ref "SV7") (pin "1") (pinfunction "K_1") (pintype "passive"))
      (node (ref "SV7") (pin "2") (pinfunction "K_2") (pintype "passive"))
      (node (ref "SV7") (pin "5") (pinfunction "K_5") (pintype "passive"))
      (node (ref "SV7") (pin "6") (pinfunction "K_6") (pintype "passive"))
      (node (ref "SV8") (pin "1") (pinfunction "K_1") (pintype "passive"))
      (node (ref "SV8") (pin "2") (pinfunction "K_2") (pintype "passive"))
      (node (ref "SV8") (pin "5") (pinfunction "K_5") (pintype "passive"))
      (node (ref "SV8") (pin "6") (pinfunction "K_6") (pintype "passive"))
      (node (ref "SW1") (pin "P$1") (pinfunction "P$1_P$1") (pintype "passive"))
      (node (ref "SW1") (pin "P$2") (pinfunction "P$1_P$2") (pintype "passive"))
      (node (ref "U1") (pin "1") (pinfunction "GND_1") (pintype "bidirectional"))
      (node (ref "U2") (pin "1") (pinfunction "GND0_1") (pintype "bidirectional"))
      (node (ref "U2") (pin "10") (pinfunction "AGND_10") (pintype "bidirectional"))
      (node (ref "U2") (pin "11") (pinfunction "GND2_11") (pintype "bidirectional"))
      (node (ref "U2") (pin "13") (pinfunction "TEST_13") (pintype "bidirectional"))
      (node (ref "U2") (pin "15") (pinfunction "GND3_15") (pintype "bidirectional"))
      (node (ref "U2") (pin "25") (pinfunction "GND4_25") (pintype "bidirectional"))
      (node (ref "U2") (pin "35") (pinfunction "GND5_35") (pintype "bidirectional"))
      (node (ref "U2") (pin "47") (pinfunction "GND6_47") (pintype "bidirectional"))
      (node (ref "U2") (pin "5") (pinfunction "GND1_5") (pintype "bidirectional"))
      (node (ref "U2") (pin "51") (pinfunction "GND7_51") (pintype "bidirectional"))
      (node (ref "U3") (pin "100") (pinfunction "GND6_100") (pintype "bidirectional"))
      (node (ref "U3") (pin "21") (pinfunction "GND1_21") (pintype "bidirectional"))
      (node (ref "U3") (pin "31") (pinfunction "GND2_31") (pintype "bidirectional"))
      (node (ref "U3") (pin "62") (pinfunction "GND3_62") (pintype "bidirectional"))
      (node (ref "U3") (pin "69") (pinfunction "GND4_69") (pintype "bidirectional"))
      (node (ref "U3") (pin "84") (pinfunction "GND5_84") (pintype "bidirectional"))
      (node (ref "U4") (pin "7") (pinfunction "VSS_7") (pintype "power_in"))
      (node (ref "U5") (pin "7") (pinfunction "VSS_7") (pintype "power_in"))
      (node (ref "U6") (pin "5") (pinfunction "GND_5") (pintype "bidirectional"))
      (node (ref "U6") (pin "7") (pinfunction "DC_7") (pintype "bidirectional"))
      (node (ref "X1") (pin "4") (pinfunction "GND_4") (pintype "bidirectional"))
      (node (ref "X1") (pin "GND") (pinfunction "GND_GND") (pintype "bidirectional"))
      (node (ref "X1") (pin "GND2") (pinfunction "GND_GND2") (pintype "bidirectional"))
      (node (ref "X2") (pin "P$1") (pinfunction "P$1_P$1") (pintype "bidirectional"))
      (node (ref "X3") (pin "P$1") (pinfunction "P$1_P$1") (pintype "bidirectional"))
      (node (ref "X4") (pin "P$1") (pinfunction "P$1_P$1") (pintype "bidirectional"))
      (node (ref "X5") (pin "P$1") (pinfunction "P$1_P$1") (pintype "bidirectional"))
    )
    (net (code "85") (name "Net-(C26-C_EL+)") (class "Default")
      (node (ref "C26") (pin "+") (pinfunction "C_EL+_+") (pintype "passive"))
      (node (ref "C30") (pin "2") (pinfunction "2_2") (pintype "passive"))
      (node (ref "L3") (pin "P$2") (pinfunction "2_P$2") (pintype "passive"))
      (node (ref "U2") (pin "9") (pinfunction "VPLL_9") (pintype "bidirectional"))
    )
    (net (code "86") (name "Net-(C27-C_EL+)") (class "Default")
      (node (ref "C27") (pin "+") (pinfunction "C_EL+_+") (pintype "passive"))
      (node (ref "C31") (pin "2") (pinfunction "2_2") (pintype "passive"))
      (node (ref "L4") (pin "P$2") (pinfunction "2_P$2") (pintype "passive"))
      (node (ref "U2") (pin "4") (pinfunction "VPHY_4") (pintype "bidirectional"))
    )
    (net (code "87") (name "Net-(D2-PadA)") (class "Default")
      (node (ref "D2") (pin "A") (pinfunction "A_A") (pintype "passive"))
      (node (ref "R11") (pin "1") (pinfunction "1_1") (pintype "passive"))
    )
    (net (code "88") (name "Net-(D3-PadA)") (class "Default")
      (node (ref "D3") (pin "A") (pinfunction "A_A") (pintype "passive"))
      (node (ref "R9") (pin "1") (pinfunction "1_1") (pintype "passive"))
    )
    (net (code "89") (name "Net-(L1-Pad1)") (class "Default")
      (node (ref "L1") (pin "1") (pinfunction "1_1") (pintype "passive"))
      (node (ref "P1") (pin "2") (pinfunction "2_2") (pintype "passive"))
    )
    (net (code "90") (name "Net-(R3-Pad1)") (class "Default")
      (node (ref "R3") (pin "1") (pinfunction "1_1") (pintype "passive"))
      (node (ref "SV3") (pin "3") (pinfunction "K_3") (pintype "passive"))
      (node (ref "SV3") (pin "4") (pinfunction "K_4") (pintype "passive"))
    )
    (net (code "91") (name "Net-(R14-Pad1)") (class "Default")
      (node (ref "R14") (pin "1") (pinfunction "1_1") (pintype "passive"))
      (node (ref "SV3") (pin "5") (pinfunction "K_5") (pintype "passive"))
      (node (ref "SV3") (pin "6") (pinfunction "K_6") (pintype "passive"))
    )
    (net (code "92") (name "Net-(R15-Pad1)") (class "Default")
      (node (ref "R15") (pin "1") (pinfunction "1_1") (pintype "passive"))
      (node (ref "SV3") (pin "7") (pinfunction "K_7") (pintype "passive"))
      (node (ref "SV3") (pin "8") (pinfunction "K_8") (pintype "passive"))
    )
    (net (code "93") (name "Net-(R16-Pad1)") (class "Default")
      (node (ref "R16") (pin "1") (pinfunction "1_1") (pintype "passive"))
      (node (ref "SV3") (pin "10") (pinfunction "K_10") (pintype "passive"))
      (node (ref "SV3") (pin "9") (pinfunction "K_9") (pintype "passive"))
    )
    (net (code "94") (name "Net-(R17-Pad1)") (class "Default")
      (node (ref "R17") (pin "1") (pinfunction "1_1") (pintype "passive"))
      (node (ref "SV3") (pin "11") (pinfunction "K_11") (pintype "passive"))
      (node (ref "SV3") (pin "12") (pinfunction "K_12") (pintype "passive"))
    )
    (net (code "95") (name "Net-(R18-Pad1)") (class "Default")
      (node (ref "R18") (pin "1") (pinfunction "1_1") (pintype "passive"))
      (node (ref "SV3") (pin "13") (pinfunction "K_13") (pintype "passive"))
      (node (ref "SV3") (pin "14") (pinfunction "K_14") (pintype "passive"))
    )
    (net (code "96") (name "Net-(R19-Pad1)") (class "Default")
      (node (ref "R19") (pin "1") (pinfunction "1_1") (pintype "passive"))
      (node (ref "SV3") (pin "15") (pinfunction "K_15") (pintype "passive"))
      (node (ref "SV3") (pin "16") (pinfunction "K_16") (pintype "passive"))
    )
    (net (code "97") (name "Net-(R20-Pad1)") (class "Default")
      (node (ref "R20") (pin "1") (pinfunction "1_1") (pintype "passive"))
      (node (ref "SV3") (pin "17") (pinfunction "K_17") (pintype "passive"))
      (node (ref "SV3") (pin "18") (pinfunction "K_18") (pintype "passive"))
    )
    (net (code "98") (name "Net-(R21-Pad1)") (class "Default")
      (node (ref "R21") (pin "1") (pinfunction "1_1") (pintype "passive"))
      (node (ref "SV3") (pin "19") (pinfunction "K_19") (pintype "passive"))
      (node (ref "SV3") (pin "20") (pinfunction "K_20") (pintype "passive"))
    )
    (net (code "99") (name "Net-(SV1A-P$1)") (class "Default")
      (node (ref "R5") (pin "1") (pinfunction "1_1") (pintype "passive"))
      (node (ref "SV1") (pin "1") (pinfunction "P$1_1") (pintype "passive"))
      (node (ref "U4") (pin "12") (pinfunction "C_12") (pintype "input"))
      (node (ref "U4") (pin "13") (pinfunction "C_13") (pintype "input"))
      (node (ref "U4") (pin "5") (pinfunction "C_5") (pintype "input"))
      (node (ref "U4") (pin "6") (pinfunction "C_6") (pintype "input"))
    )
    (net (code "100") (name "Net-(SV1C-P$1)") (class "Default")
      (node (ref "R4") (pin "2") (pinfunction "2_2") (pintype "passive"))
      (node (ref "SV1") (pin "3") (pinfunction "P$1_3") (pintype "passive"))
      (node (ref "U5") (pin "12") (pinfunction "C_12") (pintype "input"))
      (node (ref "U5") (pin "13") (pinfunction "C_13") (pintype "input"))
      (node (ref "U5") (pin "5") (pinfunction "C_5") (pintype "input"))
      (node (ref "U5") (pin "6") (pinfunction "C_6") (pintype "input"))
    )
    (net (code "101") (name "Net-(U2-OSC0)") (class "Default")
      (node (ref "C11") (pin "2") (pinfunction "2_2") (pintype "passive"))
      (node (ref "U2") (pin "3") (pinfunction "OSC0_3") (pintype "bidirectional"))
      (node (ref "XTAL1") (pin "P$2") (pinfunction "2_P$2") (pintype "passive"))
    )
    (net (code "102") (name "Net-(U2-OSCI)") (class "Default")
      (node (ref "C12") (pin "2") (pinfunction "2_2") (pintype "passive"))
      (node (ref "U2") (pin "2") (pinfunction "OSCI_2") (pintype "bidirectional"))
      (node (ref "XTAL1") (pin "P$1") (pinfunction "1_P$1") (pintype "passive"))
    )
    (net (code "103") (name "Net-(U2-REF)") (class "Default")
      (node (ref "R10") (pin "2") (pinfunction "2_2") (pintype "passive"))
      (node (ref "U2") (pin "6") (pinfunction "REF_6") (pintype "bidirectional"))
    )
    (net (code "104") (name "Net-(U2-RESET#)") (class "Default")
      (node (ref "R12") (pin "2") (pinfunction "2_2") (pintype "passive"))
      (node (ref "U2") (pin "14") (pinfunction "RESET#_14") (pintype "bidirectional"))
    )
    (net (code "105") (name "Net-(U2-VREGOUT)") (class "Default")
      (node (ref "R22") (pin "1") (pinfunction "1_1") (pintype "passive"))
      (node (ref "U2") (pin "49") (pinfunction "VREGOUT_49") (pintype "bidirectional"))
    )
    (net (code "106") (name "Net-(X1-+5V)") (class "Default")
      (node (ref "P1") (pin "1") (pinfunction "1_1") (pintype "passive"))
      (node (ref "X1") (pin "1") (pinfunction "+5V_1") (pintype "bidirectional"))
    )
    (net (code "107") (name "unconnected-(U2-PWREN#-Pad60)") (class "Default")
      (node (ref "U2") (pin "60") (pinfunction "PWREN#_60") (pintype "bidirectional"))
    )
    (net (code "108") (name "unconnected-(U2-SUSPEND#-Pad36)") (class "Default")
      (node (ref "U2") (pin "36") (pinfunction "SUSPEND#_36") (pintype "bidirectional"))
    )
    (net (code "109") (name "unconnected-(U3-NC1-Pad20)") (class "Default")
      (node (ref "U3") (pin "20") (pinfunction "NC1_20") (pintype "bidirectional"))
    )
    (net (code "110") (name "unconnected-(U3-NC2-Pad25)") (class "Default")
      (node (ref "U3") (pin "25") (pinfunction "NC2_25") (pintype "bidirectional"))
    )
    (net (code "111") (name "unconnected-(U3-NC3-Pad44)") (class "Default")
      (node (ref "U3") (pin "44") (pinfunction "NC3_44") (pintype "bidirectional"))
    )
    (net (code "112") (name "unconnected-(U3-NC4-Pad46)") (class "Default")
      (node (ref "U3") (pin "46") (pinfunction "NC4_46") (pintype "bidirectional"))
    )
    (net (code "113") (name "unconnected-(U3-NC5-Pad54)") (class "Default")
      (node (ref "U3") (pin "54") (pinfunction "NC5_54") (pintype "bidirectional"))
    )
    (net (code "114") (name "unconnected-(U3-NC6-Pad59)") (class "Default")
      (node (ref "U3") (pin "59") (pinfunction "NC6_59") (pintype "bidirectional"))
    )
    (net (code "115") (name "unconnected-(U3-NC7-Pad63)") (class "Default")
      (node (ref "U3") (pin "63") (pinfunction "NC7_63") (pintype "bidirectional"))
    )
    (net (code "116") (name "unconnected-(U3-NC8-Pad65)") (class "Default")
      (node (ref "U3") (pin "65") (pinfunction "NC8_65") (pintype "bidirectional"))
    )
    (net (code "117") (name "unconnected-(U3-NC9-Pad66)") (class "Default")
      (node (ref "U3") (pin "66") (pinfunction "NC9_66") (pintype "bidirectional"))
    )
    (net (code "118") (name "unconnected-(U3-NC10-Pad73)") (class "Default")
      (node (ref "U3") (pin "73") (pinfunction "NC10_73") (pintype "bidirectional"))
    )
    (net (code "119") (name "unconnected-(U3-NC11-Pad75)") (class "Default")
      (node (ref "U3") (pin "75") (pinfunction "NC11_75") (pintype "bidirectional"))
    )
    (net (code "120") (name "unconnected-(U3-NC12-Pad80)") (class "Default")
      (node (ref "U3") (pin "80") (pinfunction "NC12_80") (pintype "bidirectional"))
    )
    (net (code "121") (name "unconnected-(U3-NC13-Pad82)") (class "Default")
      (node (ref "U3") (pin "82") (pinfunction "NC13_82") (pintype "bidirectional"))
    )
    (net (code "122") (name "unconnected-(U3-NC14-Pad85)") (class "Default")
      (node (ref "U3") (pin "85") (pinfunction "NC14_85") (pintype "bidirectional"))
    )
    (net (code "123") (name "unconnected-(U3-NC15-Pad86)") (class "Default")
      (node (ref "U3") (pin "86") (pinfunction "NC15_86") (pintype "bidirectional"))
    )
    (net (code "124") (name "unconnected-(U3-NC16-Pad87)") (class "Default")
      (node (ref "U3") (pin "87") (pinfunction "NC16_87") (pintype "bidirectional"))
    )
    (net (code "125") (name "unconnected-(U3-NC17-Pad93)") (class "Default")
      (node (ref "U3") (pin "93") (pinfunction "NC17_93") (pintype "bidirectional"))
    )
    (net (code "126") (name "unconnected-(U3-NC18-Pad95)") (class "Default")
      (node (ref "U3") (pin "95") (pinfunction "NC18_95") (pintype "bidirectional"))
    )
    (net (code "127") (name "unconnected-(U3-NC19-Pad96)") (class "Default")
      (node (ref "U3") (pin "96") (pinfunction "NC19_96") (pintype "bidirectional"))
    )
  )
)
